# ASTABLE_555_timer.net
KiCad netlist of a schematic drawn in EAGLE
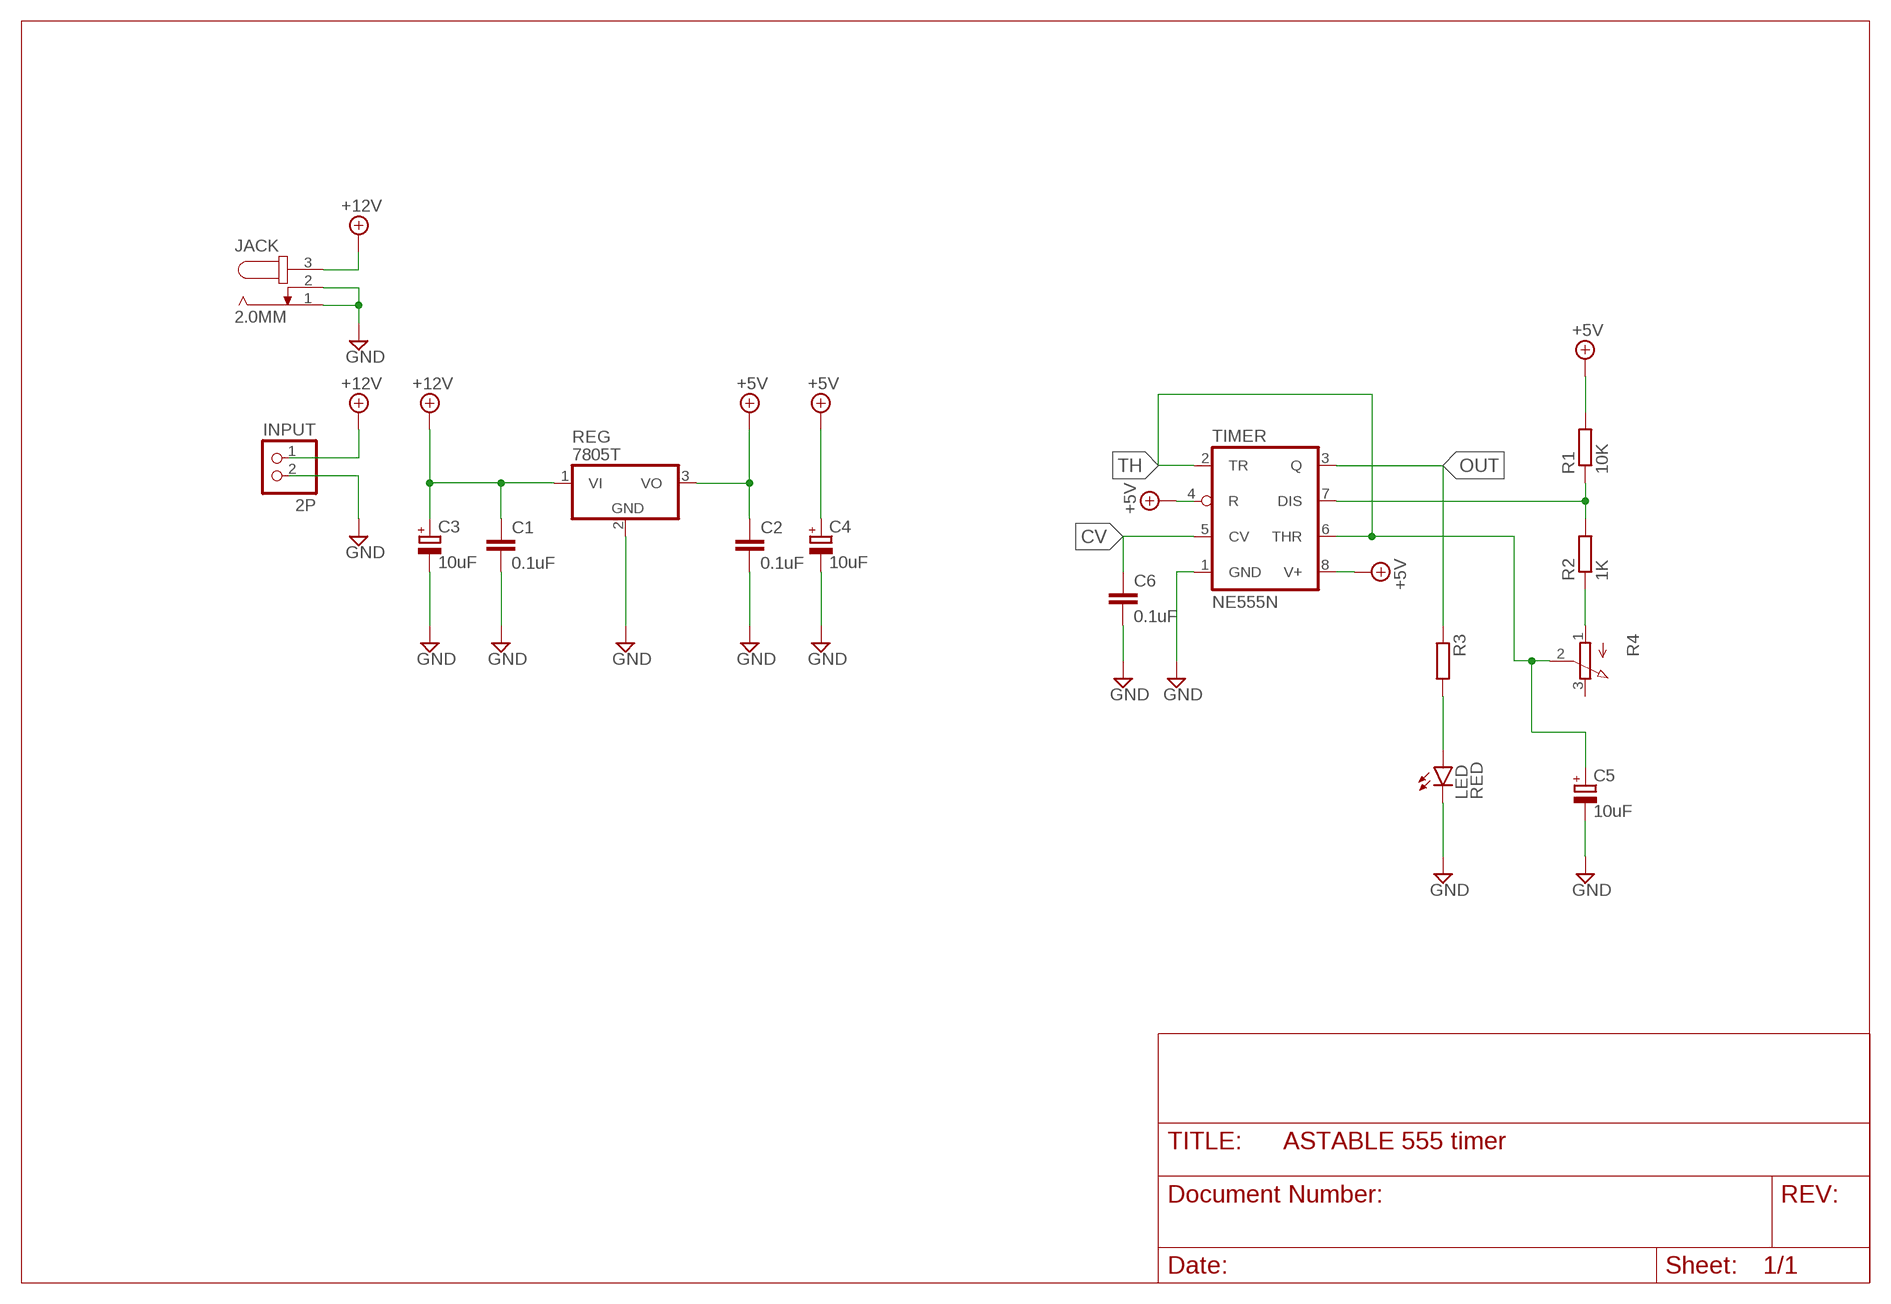
[diagram p0: schematic, sheet 1]

(export (version "E")
  (design (tool "Eeschema 10.0.6"))
  (components
    (comp (ref "C1")
      (value "0.1uF")
      (footprint "eagle-import:C050-030X075")
      (libsource (lib "eagle-import") (part "C-EU050-030X075"))
    )
    (comp (ref "C2")
      (value "0.1uF")
      (footprint "eagle-import:C050-030X075")
      (libsource (lib "eagle-import") (part "C-EU050-030X075"))
    )
    (comp (ref "C3")
      (value "10uF")
      (footprint "eagle-import:E3,5-8")
      (libsource (lib "eagle-import") (part "CPOL-EUE3.5-8"))
    )
    (comp (ref "C4")
      (value "10uF")
      (footprint "eagle-import:E3,5-8")
      (libsource (lib "eagle-import") (part "CPOL-EUE3.5-8"))
    )
    (comp (ref "C5")
      (value "10uF")
      (footprint "eagle-import:E3,5-8")
      (libsource (lib "eagle-import") (part "CPOL-EUE3.5-8"))
    )
    (comp (ref "C6")
      (value "0.1uF")
      (footprint "eagle-import:C050-030X075")
      (libsource (lib "eagle-import") (part "C-EU050-030X075"))
    )
    (comp (ref "INPUT")
      (value "2P")
      (footprint "eagle-import:1X02")
      (libsource (lib "eagle-import") (part "PINHD-1X2"))
    )
    (comp (ref "JACK")
      (value "2.0MM")
      (footprint "eagle-import:SPC4078")
      (libsource (lib "eagle-import") (part "JACK-PLUG1"))
    )
    (comp (ref "LED")
      (value "RED")
      (footprint "eagle-import:LED5MM")
      (libsource (lib "eagle-import") (part "LED5MM"))
    )
    (comp (ref "R1")
      (value "10K")
      (footprint "eagle-import:0207_10")
      (libsource (lib "eagle-import") (part "R-EU_0207/10"))
    )
    (comp (ref "R2")
      (value "1K")
      (footprint "eagle-import:0207_10")
      (libsource (lib "eagle-import") (part "R-EU_0207/10"))
    )
    (comp (ref "R3")
      (value "R-EU_0207/10")
      (footprint "eagle-import:0207_10")
      (libsource (lib "eagle-import") (part "R-EU_0207/10"))
    )
    (comp (ref "R4")
      (value "3RP/1610N")
      (footprint "eagle-import:3RP_1610N")
      (libsource (lib "eagle-import") (part "3RP/1610N"))
    )
    (comp (ref "REG")
      (value "7805T")
      (footprint "eagle-import:TO220H")
      (libsource (lib "eagle-import") (part "78T05"))
    )
    (comp (ref "TIMER")
      (value "NE555N")
      (footprint "eagle-import:DIL08")
      (libsource (lib "eagle-import") (part "555NNE"))
    )
  )
  (nets
    (net (code "1") (name "+5V") (class "Default")
      (node (ref "C2") (pin "1") (pinfunction "1_1") (pintype "passive"))
      (node (ref "C4") (pin "+") (pinfunction "+_+") (pintype "passive"))
      (node (ref "R1") (pin "2") (pinfunction "2_2") (pintype "passive"))
      (node (ref "REG") (pin "3") (pinfunction "VO_3") (pintype "passive"))
      (node (ref "TIMER") (pin "4") (pinfunction "R_4") (pintype "input"))
      (node (ref "TIMER") (pin "8") (pinfunction "V+_8") (pintype "power_in"))
    )
    (net (code "2") (name "+12V") (class "Default")
      (node (ref "C1") (pin "1") (pinfunction "1_1") (pintype "passive"))
      (node (ref "C3") (pin "+") (pinfunction "+_+") (pintype "passive"))
      (node (ref "INPUT") (pin "1") (pinfunction "1_1") (pintype "passive"))
      (node (ref "JACK") (pin "3") (pinfunction "3_3") (pintype "passive"))
      (node (ref "REG") (pin "1") (pinfunction "VI_1") (pintype "input"))
    )
    (net (code "3") (name "CV") (class "Default")
      (node (ref "C6") (pin "1") (pinfunction "1_1") (pintype "passive"))
      (node (ref "TIMER") (pin "5") (pinfunction "CV_5") (pintype "input"))
    )
    (net (code "4") (name "GND") (class "Default")
      (node (ref "C1") (pin "2") (pinfunction "2_2") (pintype "passive"))
      (node (ref "C2") (pin "2") (pinfunction "2_2") (pintype "passive"))
      (node (ref "C3") (pin "-") (pinfunction "-_-") (pintype "passive"))
      (node (ref "C4") (pin "-") (pinfunction "-_-") (pintype "passive"))
      (node (ref "C5") (pin "-") (pinfunction "-_-") (pintype "passive"))
      (node (ref "C6") (pin "2") (pinfunction "2_2") (pintype "passive"))
      (node (ref "INPUT") (pin "2") (pinfunction "2_2") (pintype "passive"))
      (node (ref "JACK") (pin "1") (pinfunction "1_1") (pintype "passive"))
      (node (ref "JACK") (pin "2") (pinfunction "2_2") (pintype "passive"))
      (node (ref "LED") (pin "K") (pinfunction "C_K") (pintype "passive"))
      (node (ref "REG") (pin "2") (pinfunction "GND_2") (pintype "passive"))
      (node (ref "TIMER") (pin "1") (pinfunction "GND_1") (pintype "power_in"))
    )
    (net (code "5") (name "Net-(LED-PadA)") (class "Default")
      (node (ref "LED") (pin "A") (pinfunction "A_A") (pintype "passive"))
      (node (ref "R3") (pin "2") (pinfunction "2_2") (pintype "passive"))
    )
    (net (code "6") (name "Net-(R4-A)") (class "Default")
      (node (ref "R2") (pin "1") (pinfunction "1_1") (pintype "passive"))
      (node (ref "R4") (pin "1") (pinfunction "A_1") (pintype "passive"))
    )
    (net (code "7") (name "Net-(TIMER-DIS)") (class "Default")
      (node (ref "R1") (pin "1") (pinfunction "1_1") (pintype "passive"))
      (node (ref "R2") (pin "2") (pinfunction "2_2") (pintype "passive"))
      (node (ref "TIMER") (pin "7") (pinfunction "DIS_7") (pintype "input"))
    )
    (net (code "8") (name "OUT") (class "Default")
      (node (ref "R3") (pin "1") (pinfunction "1_1") (pintype "passive"))
      (node (ref "TIMER") (pin "3") (pinfunction "Q_3") (pintype "output"))
    )
    (net (code "9") (name "TH") (class "Default")
      (node (ref "C5") (pin "+") (pinfunction "+_+") (pintype "passive"))
      (node (ref "R4") (pin "2") (pinfunction "S_2") (pintype "passive"))
      (node (ref "TIMER") (pin "2") (pinfunction "TR_2") (pintype "input"))
      (node (ref "TIMER") (pin "6") (pinfunction "THR_6") (pintype "input"))
    )
    (net (code "10") (name "unconnected-(R4-E-Pad3)") (class "Default")
      (node (ref "R4") (pin "3") (pinfunction "E_3") (pintype "passive"))
    )
  )
)
